# Sheet5.net
KiCad netlist of a schematic drawn in Altium Designer
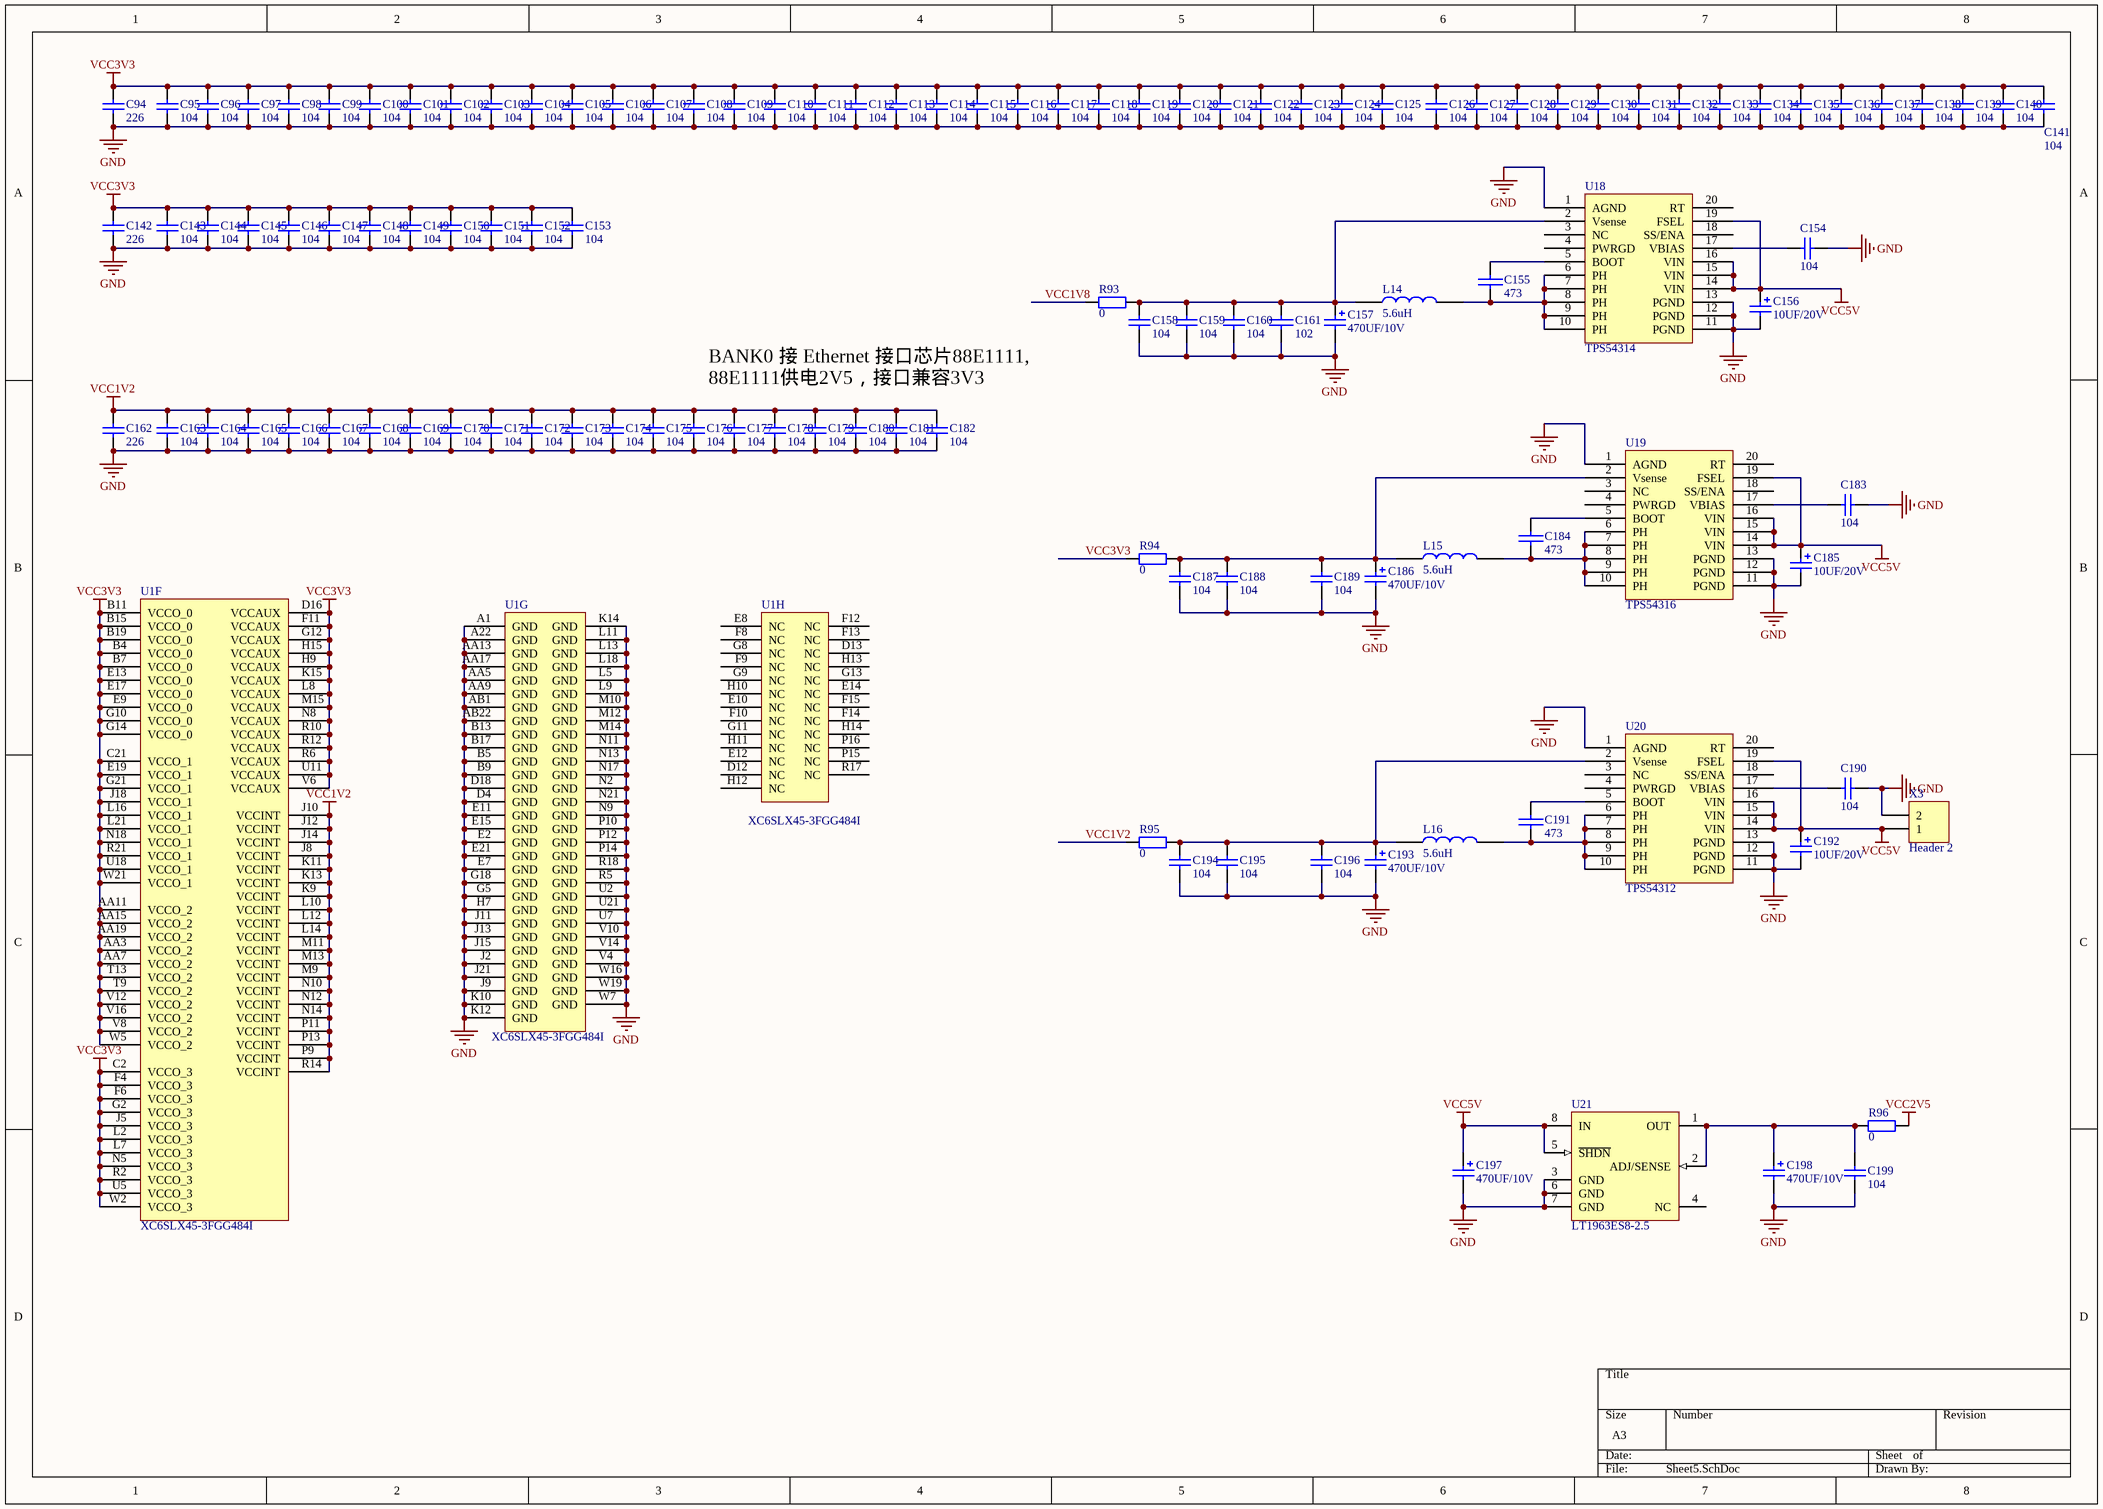
[diagram p0: Sheet5.SchDoc]

(export (version "E")
  (design (tool "Eeschema 10.0.6"))
  (components
    (comp (ref "C94")
      (value "226")
      (footprint "0603")
      (description "Capacitor")
      (fields (field (name "PUBLISHER") "Altium Limited"))
      (libsource (lib "Miscellaneous Devices") (part "Cap"))
    )
    (comp (ref "C95")
      (value "104")
      (footprint "0402")
      (description "Capacitor")
      (fields (field (name "PUBLISHER") "Altium Limited"))
      (libsource (lib "Miscellaneous Devices") (part "Cap"))
    )
    (comp (ref "C96")
      (value "104")
      (footprint "0402")
      (description "Capacitor")
      (fields (field (name "PUBLISHER") "Altium Limited"))
      (libsource (lib "Miscellaneous Devices") (part "Cap"))
    )
    (comp (ref "C97")
      (value "104")
      (footprint "0402")
      (description "Capacitor")
      (fields (field (name "PUBLISHER") "Altium Limited"))
      (libsource (lib "Miscellaneous Devices") (part "Cap"))
    )
    (comp (ref "C98")
      (value "104")
      (footprint "0402")
      (description "Capacitor")
      (fields (field (name "PUBLISHER") "Altium Limited"))
      (libsource (lib "Miscellaneous Devices") (part "Cap"))
    )
    (comp (ref "C99")
      (value "104")
      (footprint "0402")
      (description "Capacitor")
      (fields (field (name "PUBLISHER") "Altium Limited"))
      (libsource (lib "Miscellaneous Devices") (part "Cap"))
    )
    (comp (ref "C100")
      (value "104")
      (footprint "0402")
      (description "Capacitor")
      (fields (field (name "PUBLISHER") "Altium Limited"))
      (libsource (lib "Miscellaneous Devices") (part "Cap"))
    )
    (comp (ref "C101")
      (value "104")
      (footprint "0402")
      (description "Capacitor")
      (fields (field (name "PUBLISHER") "Altium Limited"))
      (libsource (lib "Miscellaneous Devices") (part "Cap"))
    )
    (comp (ref "C102")
      (value "104")
      (footprint "0402")
      (description "Capacitor")
      (fields (field (name "PUBLISHER") "Altium Limited"))
      (libsource (lib "Miscellaneous Devices") (part "Cap"))
    )
    (comp (ref "C103")
      (value "104")
      (footprint "0402")
      (description "Capacitor")
      (fields (field (name "PUBLISHER") "Altium Limited"))
      (libsource (lib "Miscellaneous Devices") (part "Cap"))
    )
    (comp (ref "C104")
      (value "104")
      (footprint "0402")
      (description "Capacitor")
      (fields (field (name "PUBLISHER") "Altium Limited"))
      (libsource (lib "Miscellaneous Devices") (part "Cap"))
    )
    (comp (ref "C105")
      (value "104")
      (footprint "0402")
      (description "Capacitor")
      (fields (field (name "PUBLISHER") "Altium Limited"))
      (libsource (lib "Miscellaneous Devices") (part "Cap"))
    )
    (comp (ref "C106")
      (value "104")
      (footprint "0402")
      (description "Capacitor")
      (fields (field (name "PUBLISHER") "Altium Limited"))
      (libsource (lib "Miscellaneous Devices") (part "Cap"))
    )
    (comp (ref "C107")
      (value "104")
      (footprint "0402")
      (description "Capacitor")
      (fields (field (name "PUBLISHER") "Altium Limited"))
      (libsource (lib "Miscellaneous Devices") (part "Cap"))
    )
    (comp (ref "C108")
      (value "104")
      (footprint "0402")
      (description "Capacitor")
      (fields (field (name "PUBLISHER") "Altium Limited"))
      (libsource (lib "Miscellaneous Devices") (part "Cap"))
    )
    (comp (ref "C109")
      (value "104")
      (footprint "0402")
      (description "Capacitor")
      (fields (field (name "PUBLISHER") "Altium Limited"))
      (libsource (lib "Miscellaneous Devices") (part "Cap"))
    )
    (comp (ref "C110")
      (value "104")
      (footprint "0402")
      (description "Capacitor")
      (fields (field (name "PUBLISHER") "Altium Limited"))
      (libsource (lib "Miscellaneous Devices") (part "Cap"))
    )
    (comp (ref "C111")
      (value "104")
      (footprint "0402")
      (description "Capacitor")
      (fields (field (name "PUBLISHER") "Altium Limited"))
      (libsource (lib "Miscellaneous Devices") (part "Cap"))
    )
    (comp (ref "C112")
      (value "104")
      (footprint "0402")
      (description "Capacitor")
      (fields (field (name "PUBLISHER") "Altium Limited"))
      (libsource (lib "Miscellaneous Devices") (part "Cap"))
    )
    (comp (ref "C113")
      (value "104")
      (footprint "0402")
      (description "Capacitor")
      (fields (field (name "PUBLISHER") "Altium Limited"))
      (libsource (lib "Miscellaneous Devices") (part "Cap"))
    )
    (comp (ref "C114")
      (value "104")
      (footprint "0402")
      (description "Capacitor")
      (fields (field (name "PUBLISHER") "Altium Limited"))
      (libsource (lib "Miscellaneous Devices") (part "Cap"))
    )
    (comp (ref "C115")
      (value "104")
      (footprint "0402")
      (description "Capacitor")
      (fields (field (name "PUBLISHER") "Altium Limited"))
      (libsource (lib "Miscellaneous Devices") (part "Cap"))
    )
    (comp (ref "C116")
      (value "104")
      (footprint "0402")
      (description "Capacitor")
      (fields (field (name "PUBLISHER") "Altium Limited"))
      (libsource (lib "Miscellaneous Devices") (part "Cap"))
    )
    (comp (ref "C117")
      (value "104")
      (footprint "0402")
      (description "Capacitor")
      (fields (field (name "PUBLISHER") "Altium Limited"))
      (libsource (lib "Miscellaneous Devices") (part "Cap"))
    )
    (comp (ref "C118")
      (value "104")
      (footprint "0402")
      (description "Capacitor")
      (fields (field (name "PUBLISHER") "Altium Limited"))
      (libsource (lib "Miscellaneous Devices") (part "Cap"))
    )
    (comp (ref "C119")
      (value "104")
      (footprint "0402")
      (description "Capacitor")
      (fields (field (name "PUBLISHER") "Altium Limited"))
      (libsource (lib "Miscellaneous Devices") (part "Cap"))
    )
    (comp (ref "C120")
      (value "104")
      (footprint "0402")
      (description "Capacitor")
      (fields (field (name "PUBLISHER") "Altium Limited"))
      (libsource (lib "Miscellaneous Devices") (part "Cap"))
    )
    (comp (ref "C121")
      (value "104")
      (footprint "0402")
      (description "Capacitor")
      (fields (field (name "PUBLISHER") "Altium Limited"))
      (libsource (lib "Miscellaneous Devices") (part "Cap"))
    )
    (comp (ref "C122")
      (value "104")
      (footprint "0402")
      (description "Capacitor")
      (fields (field (name "PUBLISHER") "Altium Limited"))
      (libsource (lib "Miscellaneous Devices") (part "Cap"))
    )
    (comp (ref "C123")
      (value "104")
      (footprint "0402")
      (description "Capacitor")
      (fields (field (name "PUBLISHER") "Altium Limited"))
      (libsource (lib "Miscellaneous Devices") (part "Cap"))
    )
    (comp (ref "C124")
      (value "104")
      (footprint "0402")
      (description "Capacitor")
      (fields (field (name "PUBLISHER") "Altium Limited"))
      (libsource (lib "Miscellaneous Devices") (part "Cap"))
    )
    (comp (ref "C125")
      (value "104")
      (footprint "0402")
      (description "Capacitor")
      (fields (field (name "PUBLISHER") "Altium Limited"))
      (libsource (lib "Miscellaneous Devices") (part "Cap"))
    )
    (comp (ref "C126")
      (value "104")
      (footprint "0402")
      (description "Capacitor")
      (fields (field (name "PUBLISHER") "Altium Limited"))
      (libsource (lib "Miscellaneous Devices") (part "Cap"))
    )
    (comp (ref "C127")
      (value "104")
      (footprint "0402")
      (description "Capacitor")
      (fields (field (name "PUBLISHER") "Altium Limited"))
      (libsource (lib "Miscellaneous Devices") (part "Cap"))
    )
    (comp (ref "C128")
      (value "104")
      (footprint "0402")
      (description "Capacitor")
      (fields (field (name "PUBLISHER") "Altium Limited"))
      (libsource (lib "Miscellaneous Devices") (part "Cap"))
    )
    (comp (ref "C129")
      (value "104")
      (footprint "0402")
      (description "Capacitor")
      (fields (field (name "PUBLISHER") "Altium Limited"))
      (libsource (lib "Miscellaneous Devices") (part "Cap"))
    )
    (comp (ref "C130")
      (value "104")
      (footprint "0402")
      (description "Capacitor")
      (fields (field (name "PUBLISHER") "Altium Limited"))
      (libsource (lib "Miscellaneous Devices") (part "Cap"))
    )
    (comp (ref "C131")
      (value "104")
      (footprint "0402")
      (description "Capacitor")
      (fields (field (name "PUBLISHER") "Altium Limited"))
      (libsource (lib "Miscellaneous Devices") (part "Cap"))
    )
    (comp (ref "C132")
      (value "104")
      (footprint "0402")
      (description "Capacitor")
      (fields (field (name "PUBLISHER") "Altium Limited"))
      (libsource (lib "Miscellaneous Devices") (part "Cap"))
    )
    (comp (ref "C133")
      (value "104")
      (footprint "0402")
      (description "Capacitor")
      (fields (field (name "PUBLISHER") "Altium Limited"))
      (libsource (lib "Miscellaneous Devices") (part "Cap"))
    )
    (comp (ref "C134")
      (value "104")
      (footprint "0402")
      (description "Capacitor")
      (fields (field (name "PUBLISHER") "Altium Limited"))
      (libsource (lib "Miscellaneous Devices") (part "Cap"))
    )
    (comp (ref "C135")
      (value "104")
      (footprint "0402")
      (description "Capacitor")
      (fields (field (name "PUBLISHER") "Altium Limited"))
      (libsource (lib "Miscellaneous Devices") (part "Cap"))
    )
    (comp (ref "C136")
      (value "104")
      (footprint "0402")
      (description "Capacitor")
      (fields (field (name "PUBLISHER") "Altium Limited"))
      (libsource (lib "Miscellaneous Devices") (part "Cap"))
    )
    (comp (ref "C137")
      (value "104")
      (footprint "0402")
      (description "Capacitor")
      (fields (field (name "PUBLISHER") "Altium Limited"))
      (libsource (lib "Miscellaneous Devices") (part "Cap"))
    )
    (comp (ref "C138")
      (value "104")
      (footprint "0402")
      (description "Capacitor")
      (fields (field (name "PUBLISHER") "Altium Limited"))
      (libsource (lib "Miscellaneous Devices") (part "Cap"))
    )
    (comp (ref "C139")
      (value "104")
      (footprint "0402")
      (description "Capacitor")
      (fields (field (name "PUBLISHER") "Altium Limited"))
      (libsource (lib "Miscellaneous Devices") (part "Cap"))
    )
    (comp (ref "C140")
      (value "104")
      (footprint "0402")
      (description "Capacitor")
      (fields (field (name "PUBLISHER") "Altium Limited"))
      (libsource (lib "Miscellaneous Devices") (part "Cap"))
    )
    (comp (ref "C141")
      (value "104")
      (footprint "0402")
      (description "Capacitor")
      (fields (field (name "PUBLISHER") "Altium Limited"))
      (libsource (lib "Miscellaneous Devices") (part "Cap"))
    )
    (comp (ref "C142")
      (value "226")
      (footprint "0603")
      (description "Capacitor")
      (fields (field (name "PUBLISHER") "Altium Limited"))
      (libsource (lib "Miscellaneous Devices") (part "Cap"))
    )
    (comp (ref "C143")
      (value "104")
      (footprint "0402")
      (description "Capacitor")
      (fields (field (name "PUBLISHER") "Altium Limited"))
      (libsource (lib "Miscellaneous Devices") (part "Cap"))
    )
    (comp (ref "C144")
      (value "104")
      (footprint "0402")
      (description "Capacitor")
      (fields (field (name "PUBLISHER") "Altium Limited"))
      (libsource (lib "Miscellaneous Devices") (part "Cap"))
    )
    (comp (ref "C145")
      (value "104")
      (footprint "0402")
      (description "Capacitor")
      (fields (field (name "PUBLISHER") "Altium Limited"))
      (libsource (lib "Miscellaneous Devices") (part "Cap"))
    )
    (comp (ref "C146")
      (value "104")
      (footprint "0402")
      (description "Capacitor")
      (fields (field (name "PUBLISHER") "Altium Limited"))
      (libsource (lib "Miscellaneous Devices") (part "Cap"))
    )
    (comp (ref "C147")
      (value "104")
      (footprint "0402")
      (description "Capacitor")
      (fields (field (name "PUBLISHER") "Altium Limited"))
      (libsource (lib "Miscellaneous Devices") (part "Cap"))
    )
    (comp (ref "C148")
      (value "104")
      (footprint "0402")
      (description "Capacitor")
      (fields (field (name "PUBLISHER") "Altium Limited"))
      (libsource (lib "Miscellaneous Devices") (part "Cap"))
    )
    (comp (ref "C149")
      (value "104")
      (footprint "0402")
      (description "Capacitor")
      (fields (field (name "PUBLISHER") "Altium Limited"))
      (libsource (lib "Miscellaneous Devices") (part "Cap"))
    )
    (comp (ref "C150")
      (value "104")
      (footprint "0402")
      (description "Capacitor")
      (fields (field (name "PUBLISHER") "Altium Limited"))
      (libsource (lib "Miscellaneous Devices") (part "Cap"))
    )
    (comp (ref "C151")
      (value "104")
      (footprint "0402")
      (description "Capacitor")
      (fields (field (name "PUBLISHER") "Altium Limited"))
      (libsource (lib "Miscellaneous Devices") (part "Cap"))
    )
    (comp (ref "C152")
      (value "104")
      (footprint "0402")
      (description "Capacitor")
      (fields (field (name "PUBLISHER") "Altium Limited"))
      (libsource (lib "Miscellaneous Devices") (part "Cap"))
    )
    (comp (ref "C153")
      (value "104")
      (footprint "0402")
      (description "Capacitor")
      (fields (field (name "PUBLISHER") "Altium Limited"))
      (libsource (lib "Miscellaneous Devices") (part "Cap"))
    )
    (comp (ref "C154")
      (value "104")
      (footprint "0402")
      (description "Capacitor")
      (fields (field (name "PUBLISHER") "Altium Limited"))
      (libsource (lib "Miscellaneous Devices") (part "Cap"))
    )
    (comp (ref "C155")
      (value "473")
      (footprint "0402")
      (description "Capacitor")
      (libsource (lib "*") (part "CAP"))
    )
    (comp (ref "C156")
      (value "10UF/20V")
      (footprint "CAP-B")
      (description "Polarized Capacitor (Axial)")
      (fields (field (name "PUBLISHER") "Altium Limited"))
      (libsource (lib "Miscellaneous Devices") (part "Cap Pol2"))
    )
    (comp (ref "C157")
      (value "470UF/10V")
      (footprint "CAP-D")
      (description "Polarized Capacitor (Axial)")
      (fields (field (name "PUBLISHER") "Altium Limited"))
      (libsource (lib "Miscellaneous Devices") (part "Cap Pol2"))
    )
    (comp (ref "C158")
      (value "104")
      (footprint "0402")
      (description "Capacitor")
      (fields (field (name "PUBLISHER") "Altium Limited"))
      (libsource (lib "Miscellaneous Devices") (part "Cap"))
    )
    (comp (ref "C159")
      (value "104")
      (footprint "0402")
      (description "Capacitor")
      (fields (field (name "PUBLISHER") "Altium Limited"))
      (libsource (lib "Miscellaneous Devices") (part "Cap"))
    )
    (comp (ref "C160")
      (value "104")
      (footprint "0402")
      (description "Capacitor")
      (fields (field (name "PUBLISHER") "Altium Limited"))
      (libsource (lib "Miscellaneous Devices") (part "Cap"))
    )
    (comp (ref "C161")
      (value "102")
      (footprint "0402")
      (description "Capacitor")
      (libsource (lib "*") (part "CAP"))
    )
    (comp (ref "C162")
      (value "226")
      (footprint "0603")
      (description "Capacitor")
      (fields (field (name "PUBLISHER") "Altium Limited"))
      (libsource (lib "Miscellaneous Devices") (part "Cap"))
    )
    (comp (ref "C163")
      (value "104")
      (footprint "0402")
      (description "Capacitor")
      (fields (field (name "PUBLISHER") "Altium Limited"))
      (libsource (lib "Miscellaneous Devices") (part "Cap"))
    )
    (comp (ref "C164")
      (value "104")
      (footprint "0402")
      (description "Capacitor")
      (fields (field (name "PUBLISHER") "Altium Limited"))
      (libsource (lib "Miscellaneous Devices") (part "Cap"))
    )
    (comp (ref "C165")
      (value "104")
      (footprint "0402")
      (description "Capacitor")
      (fields (field (name "PUBLISHER") "Altium Limited"))
      (libsource (lib "Miscellaneous Devices") (part "Cap"))
    )
    (comp (ref "C166")
      (value "104")
      (footprint "0402")
      (description "Capacitor")
      (fields (field (name "PUBLISHER") "Altium Limited"))
      (libsource (lib "Miscellaneous Devices") (part "Cap"))
    )
    (comp (ref "C167")
      (value "104")
      (footprint "0402")
      (description "Capacitor")
      (fields (field (name "PUBLISHER") "Altium Limited"))
      (libsource (lib "Miscellaneous Devices") (part "Cap"))
    )
    (comp (ref "C168")
      (value "104")
      (footprint "0402")
      (description "Capacitor")
      (fields (field (name "PUBLISHER") "Altium Limited"))
      (libsource (lib "Miscellaneous Devices") (part "Cap"))
    )
    (comp (ref "C169")
      (value "104")
      (footprint "0402")
      (description "Capacitor")
      (fields (field (name "PUBLISHER") "Altium Limited"))
      (libsource (lib "Miscellaneous Devices") (part "Cap"))
    )
    (comp (ref "C170")
      (value "104")
      (footprint "0402")
      (description "Capacitor")
      (fields (field (name "PUBLISHER") "Altium Limited"))
      (libsource (lib "Miscellaneous Devices") (part "Cap"))
    )
    (comp (ref "C171")
      (value "104")
      (footprint "0402")
      (description "Capacitor")
      (fields (field (name "PUBLISHER") "Altium Limited"))
      (libsource (lib "Miscellaneous Devices") (part "Cap"))
    )
    (comp (ref "C172")
      (value "104")
      (footprint "0402")
      (description "Capacitor")
      (fields (field (name "PUBLISHER") "Altium Limited"))
      (libsource (lib "Miscellaneous Devices") (part "Cap"))
    )
    (comp (ref "C173")
      (value "104")
      (footprint "0402")
      (description "Capacitor")
      (fields (field (name "PUBLISHER") "Altium Limited"))
      (libsource (lib "Miscellaneous Devices") (part "Cap"))
    )
    (comp (ref "C174")
      (value "104")
      (footprint "0402")
      (description "Capacitor")
      (fields (field (name "PUBLISHER") "Altium Limited"))
      (libsource (lib "Miscellaneous Devices") (part "Cap"))
    )
    (comp (ref "C175")
      (value "104")
      (footprint "0402")
      (description "Capacitor")
      (fields (field (name "PUBLISHER") "Altium Limited"))
      (libsource (lib "Miscellaneous Devices") (part "Cap"))
    )
    (comp (ref "C176")
      (value "104")
      (footprint "0402")
      (description "Capacitor")
      (fields (field (name "PUBLISHER") "Altium Limited"))
      (libsource (lib "Miscellaneous Devices") (part "Cap"))
    )
    (comp (ref "C177")
      (value "104")
      (footprint "0402")
      (description "Capacitor")
      (fields (field (name "PUBLISHER") "Altium Limited"))
      (libsource (lib "Miscellaneous Devices") (part "Cap"))
    )
    (comp (ref "C178")
      (value "104")
      (footprint "0402")
      (description "Capacitor")
      (fields (field (name "PUBLISHER") "Altium Limited"))
      (libsource (lib "Miscellaneous Devices") (part "Cap"))
    )
    (comp (ref "C179")
      (value "104")
      (footprint "0402")
      (description "Capacitor")
      (fields (field (name "PUBLISHER") "Altium Limited"))
      (libsource (lib "Miscellaneous Devices") (part "Cap"))
    )
    (comp (ref "C180")
      (value "104")
      (footprint "0402")
      (description "Capacitor")
      (fields (field (name "PUBLISHER") "Altium Limited"))
      (libsource (lib "Miscellaneous Devices") (part "Cap"))
    )
    (comp (ref "C181")
      (value "104")
      (footprint "0402")
      (description "Capacitor")
      (fields (field (name "PUBLISHER") "Altium Limited"))
      (libsource (lib "Miscellaneous Devices") (part "Cap"))
    )
    (comp (ref "C182")
      (value "104")
      (footprint "0402")
      (description "Capacitor")
      (fields (field (name "PUBLISHER") "Altium Limited"))
      (libsource (lib "Miscellaneous Devices") (part "Cap"))
    )
    (comp (ref "C183")
      (value "104")
      (footprint "0402")
      (description "Capacitor")
      (fields (field (name "PUBLISHER") "Altium Limited"))
      (libsource (lib "Miscellaneous Devices") (part "Cap"))
    )
    (comp (ref "C184")
      (value "473")
      (footprint "0402")
      (description "Capacitor")
      (libsource (lib "*") (part "CAP"))
    )
    (comp (ref "C185")
      (value "10UF/20V")
      (footprint "CAP-B")
      (description "Polarized Capacitor (Axial)")
      (fields (field (name "PUBLISHER") "Altium Limited"))
      (libsource (lib "Miscellaneous Devices") (part "Cap Pol2"))
    )
    (comp (ref "C186")
      (value "470UF/10V")
      (footprint "CAP-D")
      (description "Polarized Capacitor (Axial)")
      (fields (field (name "PUBLISHER") "Altium Limited"))
      (libsource (lib "Miscellaneous Devices") (part "Cap Pol2"))
    )
    (comp (ref "C187")
      (value "104")
      (footprint "0402")
      (description "Capacitor")
      (fields (field (name "PUBLISHER") "Altium Limited"))
      (libsource (lib "Miscellaneous Devices") (part "Cap"))
    )
    (comp (ref "C188")
      (value "104")
      (footprint "0402")
      (description "Capacitor")
      (fields (field (name "PUBLISHER") "Altium Limited"))
      (libsource (lib "Miscellaneous Devices") (part "Cap"))
    )
    (comp (ref "C189")
      (value "104")
      (footprint "0402")
      (description "Capacitor")
      (fields (field (name "PUBLISHER") "Altium Limited"))
      (libsource (lib "Miscellaneous Devices") (part "Cap"))
    )
    (comp (ref "C190")
      (value "104")
      (footprint "0402")
      (description "Capacitor")
      (fields (field (name "PUBLISHER") "Altium Limited"))
      (libsource (lib "Miscellaneous Devices") (part "Cap"))
    )
    (comp (ref "C191")
      (value "473")
      (footprint "0402")
      (description "Capacitor")
      (libsource (lib "*") (part "CAP"))
    )
    (comp (ref "C192")
      (value "10UF/20V")
      (footprint "CAP-B")
      (description "Polarized Capacitor (Axial)")
      (fields (field (name "PUBLISHER") "Altium Limited"))
      (libsource (lib "Miscellaneous Devices") (part "Cap Pol2"))
    )
    (comp (ref "C193")
      (value "470UF/10V")
      (footprint "CAP-D")
      (description "Polarized Capacitor (Axial)")
      (fields (field (name "PUBLISHER") "Altium Limited"))
      (libsource (lib "Miscellaneous Devices") (part "Cap Pol2"))
    )
    (comp (ref "C194")
      (value "104")
      (footprint "0402")
      (description "Capacitor")
      (fields (field (name "PUBLISHER") "Altium Limited"))
      (libsource (lib "Miscellaneous Devices") (part "Cap"))
    )
    (comp (ref "C195")
      (value "104")
      (footprint "0402")
      (description "Capacitor")
      (fields (field (name "PUBLISHER") "Altium Limited"))
      (libsource (lib "Miscellaneous Devices") (part "Cap"))
    )
    (comp (ref "C196")
      (value "104")
      (footprint "0402")
      (description "Capacitor")
      (fields (field (name "PUBLISHER") "Altium Limited"))
      (libsource (lib "Miscellaneous Devices") (part "Cap"))
    )
    (comp (ref "C197")
      (value "470UF/10V")
      (footprint "CAP-D")
      (description "Polarized Capacitor (Axial)")
      (fields (field (name "PUBLISHER") "Altium Limited"))
      (libsource (lib "Miscellaneous Devices") (part "Cap Pol2"))
    )
    (comp (ref "C198")
      (value "470UF/10V")
      (footprint "CAP-D")
      (description "Polarized Capacitor (Axial)")
      (fields (field (name "PUBLISHER") "Altium Limited"))
      (libsource (lib "Miscellaneous Devices") (part "Cap Pol2"))
    )
    (comp (ref "C199")
      (value "104")
      (footprint "0402")
      (description "Capacitor")
      (fields (field (name "PUBLISHER") "Altium Limited"))
      (libsource (lib "Miscellaneous Devices") (part "Cap"))
    )
    (comp (ref "L14") (value "5.6uH") (footprint "L5R2") (libsource (lib "*") (part "INDUCTOR1")))
    (comp (ref "L15") (value "5.6uH") (footprint "L5R2") (libsource (lib "*") (part "INDUCTOR1")))
    (comp (ref "L16") (value "5.6uH") (footprint "L5R2") (libsource (lib "*") (part "INDUCTOR1")))
    (comp (ref "R93")
      (value "0")
      (footprint "0603")
      (description "Resistor")
      (fields (field (name "PUBLISHER") "Altium Limited"))
      (libsource (lib "Miscellaneous Devices") (part "Res2"))
    )
    (comp (ref "R94")
      (value "0")
      (footprint "0603")
      (description "Resistor")
      (fields (field (name "PUBLISHER") "Altium Limited"))
      (libsource (lib "Miscellaneous Devices") (part "Res2"))
    )
    (comp (ref "R95")
      (value "0")
      (footprint "0603")
      (description "Resistor")
      (fields (field (name "PUBLISHER") "Altium Limited"))
      (libsource (lib "Miscellaneous Devices") (part "Res2"))
    )
    (comp (ref "R96")
      (value "0")
      (footprint "0603")
      (description "Resistor")
      (fields (field (name "PUBLISHER") "Altium Limited"))
      (libsource (lib "Miscellaneous Devices") (part "Res2"))
    )
    (comp (ref "U1")
      (value "XC6SLX45-3FGG484I")
      (footprint "FGG484")
      (fields (field (name "PUBLISHER") "Altium Limited"))
      (libsource (lib "Xilinx Spartan-6") (part "XC6SLX45-3FGG484I"))
    )
    (comp (ref "U18")
      (value "TPS54314")
      (footprint "SOP20")
      (description "TPS54312")
      (libsource (lib "*") (part "TPS54312"))
    )
    (comp (ref "U19")
      (value "TPS54316")
      (footprint "SOP20")
      (description "TPS54312")
      (libsource (lib "*") (part "TPS54312"))
    )
    (comp (ref "U20") (value "TPS54312") (footprint "SOP20") (libsource (lib "*") (part "TPS54312")))
    (comp (ref "U21")
      (value "LT1963ES8-2.5")
      (footprint "so_8")
      (description "300mA, Low Noise, Micropower Low Dropout Regulator")
      (fields (field (name "PUBLISHER") "Altium Limited"))
      (libsource (lib "Mpd_Fpga_2") (part "LT1962EMS8"))
    )
    (comp (ref "X3")
      (value "Header 2")
      (footprint "HDR1X2")
      (description "Header, 2-Pin")
      (fields (field (name "PUBLISHER") "Altium Limited"))
      (libsource (lib "Miscellaneous Connectors") (part "Header 2"))
    )
  )
  (nets
    (net (code "1") (name "/VCC1V8") (class "Default")
      (node (ref "R93") (pin "2") (pinfunction "2_2") (pintype "passive"))
    )
    (net (code "2") (name "GND") (class "Default")
      (node (ref "C100") (pin "1") (pinfunction "1_1") (pintype "passive"))
      (node (ref "C101") (pin "1") (pinfunction "1_1") (pintype "passive"))
      (node (ref "C102") (pin "1") (pinfunction "1_1") (pintype "passive"))
      (node (ref "C103") (pin "1") (pinfunction "1_1") (pintype "passive"))
      (node (ref "C104") (pin "1") (pinfunction "1_1") (pintype "passive"))
      (node (ref "C105") (pin "1") (pinfunction "1_1") (pintype "passive"))
      (node (ref "C106") (pin "1") (pinfunction "1_1") (pintype "passive"))
      (node (ref "C107") (pin "1") (pinfunction "1_1") (pintype "passive"))
      (node (ref "C108") (pin "1") (pinfunction "1_1") (pintype "passive"))
      (node (ref "C109") (pin "1") (pinfunction "1_1") (pintype "passive"))
      (node (ref "C110") (pin "1") (pinfunction "1_1") (pintype "passive"))
      (node (ref "C111") (pin "1") (pinfunction "1_1") (pintype "passive"))
      (node (ref "C112") (pin "1") (pinfunction "1_1") (pintype "passive"))
      (node (ref "C113") (pin "1") (pinfunction "1_1") (pintype "passive"))
      (node (ref "C114") (pin "1") (pinfunction "1_1") (pintype "passive"))
      (node (ref "C115") (pin "1") (pinfunction "1_1") (pintype "passive"))
      (node (ref "C116") (pin "1") (pinfunction "1_1") (pintype "passive"))
      (node (ref "C117") (pin "1") (pinfunction "1_1") (pintype "passive"))
      (node (ref "C118") (pin "1") (pinfunction "1_1") (pintype "passive"))
      (node (ref "C119") (pin "1") (pinfunction "1_1") (pintype "passive"))
      (node (ref "C120") (pin "1") (pinfunction "1_1") (pintype "passive"))
      (node (ref "C121") (pin "1") (pinfunction "1_1") (pintype "passive"))
      (node (ref "C122") (pin "1") (pinfunction "1_1") (pintype "passive"))
      (node (ref "C123") (pin "1") (pinfunction "1_1") (pintype "passive"))
      (node (ref "C124") (pin "1") (pinfunction "1_1") (pintype "passive"))
      (node (ref "C125") (pin "1") (pinfunction "1_1") (pintype "passive"))
      (node (ref "C126") (pin "1") (pinfunction "1_1") (pintype "passive"))
      (node (ref "C127") (pin "1") (pinfunction "1_1") (pintype "passive"))
      (node (ref "C128") (pin "1") (pinfunction "1_1") (pintype "passive"))
      (node (ref "C129") (pin "1") (pinfunction "1_1") (pintype "passive"))
      (node (ref "C130") (pin "1") (pinfunction "1_1") (pintype "passive"))
      (node (ref "C131") (pin "1") (pinfunction "1_1") (pintype "passive"))
      (node (ref "C132") (pin "1") (pinfunction "1_1") (pintype "passive"))
      (node (ref "C133") (pin "1") (pinfunction "1_1") (pintype "passive"))
      (node (ref "C134") (pin "1") (pinfunction "1_1") (pintype "passive"))
      (node (ref "C135") (pin "1") (pinfunction "1_1") (pintype "passive"))
      (node (ref "C136") (pin "1") (pinfunction "1_1") (pintype "passive"))
      (node (ref "C137") (pin "1") (pinfunction "1_1") (pintype "passive"))
      (node (ref "C138") (pin "1") (pinfunction "1_1") (pintype "passive"))
      (node (ref "C139") (pin "1") (pinfunction "1_1") (pintype "passive"))
      (node (ref "C140") (pin "1") (pinfunction "1_1") (pintype "passive"))
      (node (ref "C141") (pin "1") (pinfunction "1_1") (pintype "passive"))
      (node (ref "C142") (pin "1") (pinfunction "1_1") (pintype "passive"))
      (node (ref "C143") (pin "1") (pinfunction "1_1") (pintype "passive"))
      (node (ref "C144") (pin "1") (pinfunction "1_1") (pintype "passive"))
      (node (ref "C145") (pin "1") (pinfunction "1_1") (pintype "passive"))
      (node (ref "C146") (pin "1") (pinfunction "1_1") (pintype "passive"))
      (node (ref "C147") (pin "1") (pinfunction "1_1") (pintype "passive"))
      (node (ref "C148") (pin "1") (pinfunction "1_1") (pintype "passive"))
      (node (ref "C149") (pin "1") (pinfunction "1_1") (pintype "passive"))
      (node (ref "C150") (pin "1") (pinfunction "1_1") (pintype "passive"))
      (node (ref "C151") (pin "1") (pinfunction "1_1") (pintype "passive"))
      (node (ref "C152") (pin "1") (pinfunction "1_1") (pintype "passive"))
      (node (ref "C153") (pin "1") (pinfunction "1_1") (pintype "passive"))
      (node (ref "C154") (pin "1") (pinfunction "1_1") (pintype "passive"))
      (node (ref "C156") (pin "2") (pinfunction "2_2") (pintype "passive"))
      (node (ref "C157") (pin "2") (pinfunction "2_2") (pintype "passive"))
      (node (ref "C158") (pin "1") (pinfunction "1_1") (pintype "passive"))
      (node (ref "C159") (pin "1") (pinfunction "1_1") (pintype "passive"))
      (node (ref "C160") (pin "1") (pinfunction "1_1") (pintype "passive"))
      (node (ref "C161") (pin "1") (pinfunction "1_1") (pintype "passive"))
      (node (ref "C162") (pin "1") (pinfunction "1_1") (pintype "passive"))
      (node (ref "C163") (pin "1") (pinfunction "1_1") (pintype "passive"))
      (node (ref "C164") (pin "1") (pinfunction "1_1") (pintype "passive"))
      (node (ref "C165") (pin "1") (pinfunction "1_1") (pintype "passive"))
      (node (ref "C166") (pin "1") (pinfunction "1_1") (pintype "passive"))
      (node (ref "C167") (pin "1") (pinfunction "1_1") (pintype "passive"))
      (node (ref "C168") (pin "1") (pinfunction "1_1") (pintype "passive"))
      (node (ref "C169") (pin "1") (pinfunction "1_1") (pintype "passive"))
      (node (ref "C170") (pin "1") (pinfunction "1_1") (pintype "passive"))
      (node (ref "C171") (pin "1") (pinfunction "1_1") (pintype "passive"))
      (node (ref "C172") (pin "1") (pinfunction "1_1") (pintype "passive"))
      (node (ref "C173") (pin "1") (pinfunction "1_1") (pintype "passive"))
      (node (ref "C174") (pin "1") (pinfunction "1_1") (pintype "passive"))
      (node (ref "C175") (pin "1") (pinfunction "1_1") (pintype "passive"))
      (node (ref "C176") (pin "1") (pinfunction "1_1") (pintype "passive"))
      (node (ref "C177") (pin "1") (pinfunction "1_1") (pintype "passive"))
      (node (ref "C178") (pin "1") (pinfunction "1_1") (pintype "passive"))
      (node (ref "C179") (pin "1") (pinfunction "1_1") (pintype "passive"))
      (node (ref "C180") (pin "1") (pinfunction "1_1") (pintype "passive"))
      (node (ref "C181") (pin "1") (pinfunction "1_1") (pintype "passive"))
      (node (ref "C182") (pin "1") (pinfunction "1_1") (pintype "passive"))
      (node (ref "C183") (pin "1") (pinfunction "1_1") (pintype "passive"))
      (node (ref "C185") (pin "2") (pinfunction "2_2") (pintype "passive"))
      (node (ref "C186") (pin "2") (pinfunction "2_2") (pintype "passive"))
      (node (ref "C187") (pin "1") (pinfunction "1_1") (pintype "passive"))
      (node (ref "C188") (pin "1") (pinfunction "1_1") (pintype "passive"))
      (node (ref "C189") (pin "1") (pinfunction "1_1") (pintype "passive"))
      (node (ref "C190") (pin "1") (pinfunction "1_1") (pintype "passive"))
      (node (ref "C192") (pin "2") (pinfunction "2_2") (pintype "passive"))
      (node (ref "C193") (pin "2") (pinfunction "2_2") (pintype "passive"))
      (node (ref "C194") (pin "1") (pinfunction "1_1") (pintype "passive"))
      (node (ref "C195") (pin "1") (pinfunction "1_1") (pintype "passive"))
      (node (ref "C196") (pin "1") (pinfunction "1_1") (pintype "passive"))
      (node (ref "C197") (pin "2") (pinfunction "2_2") (pintype "passive"))
      (node (ref "C198") (pin "2") (pinfunction "2_2") (pintype "passive"))
      (node (ref "C199") (pin "1") (pinfunction "1_1") (pintype "passive"))
      (node (ref "C94") (pin "1") (pinfunction "1_1") (pintype "passive"))
      (node (ref "C95") (pin "1") (pinfunction "1_1") (pintype "passive"))
      (node (ref "C96") (pin "1") (pinfunction "1_1") (pintype "passive"))
      (node (ref "C97") (pin "1") (pinfunction "1_1") (pintype "passive"))
      (node (ref "C98") (pin "1") (pinfunction "1_1") (pintype "passive"))
      (node (ref "C99") (pin "1") (pinfunction "1_1") (pintype "passive"))
      (node (ref "U1") (pin "A1") (pinfunction "GND_A1") (pintype "power_in"))
      (node (ref "U1") (pin "A22") (pinfunction "GND_A22") (pintype "power_in"))
      (node (ref "U1") (pin "AA13") (pinfunction "GND_AA13") (pintype "power_in"))
      (node (ref "U1") (pin "AA17") (pinfunction "GND_AA17") (pintype "power_in"))
      (node (ref "U1") (pin "AA5") (pinfunction "GND_AA5") (pintype "power_in"))
      (node (ref "U1") (pin "AA9") (pinfunction "GND_AA9") (pintype "power_in"))
      (node (ref "U1") (pin "AB1") (pinfunction "GND_AB1") (pintype "power_in"))
      (node (ref "U1") (pin "AB22") (pinfunction "GND_AB22") (pintype "power_in"))
      (node (ref "U1") (pin "B13") (pinfunction "GND_B13") (pintype "power_in"))
      (node (ref "U1") (pin "B17") (pinfunction "GND_B17") (pintype "power_in"))
      (node (ref "U1") (pin "B5") (pinfunction "GND_B5") (pintype "power_in"))
      (node (ref "U1") (pin "B9") (pinfunction "GND_B9") (pintype "power_in"))
      (node (ref "U1") (pin "D18") (pinfunction "GND_D18") (pintype "power_in"))
      (node (ref "U1") (pin "D4") (pinfunction "GND_D4") (pintype "power_in"))
      (node (ref "U1") (pin "E11") (pinfunction "GND_E11") (pintype "power_in"))
      (node (ref "U1") (pin "E15") (pinfunction "GND_E15") (pintype "power_in"))
      (node (ref "U1") (pin "E2") (pinfunction "GND_E2") (pintype "power_in"))
      (node (ref "U1") (pin "E21") (pinfunction "GND_E21") (pintype "power_in"))
      (node (ref "U1") (pin "E7") (pinfunction "GND_E7") (pintype "power_in"))
      (node (ref "U1") (pin "G18") (pinfunction "GND_G18") (pintype "power_in"))
      (node (ref "U1") (pin "G5") (pinfunction "GND_G5") (pintype "power_in"))
      (node (ref "U1") (pin "H7") (pinfunction "GND_H7") (pintype "power_in"))
      (node (ref "U1") (pin "J11") (pinfunction "GND_J11") (pintype "power_in"))
      (node (ref "U1") (pin "J13") (pinfunction "GND_J13") (pintype "power_in"))
      (node (ref "U1") (pin "J15") (pinfunction "GND_J15") (pintype "power_in"))
      (node (ref "U1") (pin "J2") (pinfunction "GND_J2") (pintype "power_in"))
      (node (ref "U1") (pin "J21") (pinfunction "GND_J21") (pintype "power_in"))
      (node (ref "U1") (pin "J9") (pinfunction "GND_J9") (pintype "power_in"))
      (node (ref "U1") (pin "K10") (pinfunction "GND_K10") (pintype "power_in"))
      (node (ref "U1") (pin "K12") (pinfunction "GND_K12") (pintype "power_in"))
      (node (ref "U1") (pin "K14") (pinfunction "GND_K14") (pintype "power_in"))
      (node (ref "U1") (pin "L11") (pinfunction "GND_L11") (pintype "power_in"))
      (node (ref "U1") (pin "L13") (pinfunction "GND_L13") (pintype "power_in"))
      (node (ref "U1") (pin "L18") (pinfunction "GND_L18") (pintype "power_in"))
      (node (ref "U1") (pin "L5") (pinfunction "GND_L5") (pintype "power_in"))
      (node (ref "U1") (pin "L9") (pinfunction "GND_L9") (pintype "power_in"))
      (node (ref "U1") (pin "M10") (pinfunction "GND_M10") (pintype "power_in"))
      (node (ref "U1") (pin "M12") (pinfunction "GND_M12") (pintype "power_in"))
      (node (ref "U1") (pin "M14") (pinfunction "GND_M14") (pintype "power_in"))
      (node (ref "U1") (pin "N11") (pinfunction "GND_N11") (pintype "power_in"))
      (node (ref "U1") (pin "N13") (pinfunction "GND_N13") (pintype "power_in"))
      (node (ref "U1") (pin "N17") (pinfunction "GND_N17") (pintype "power_in"))
      (node (ref "U1") (pin "N2") (pinfunction "GND_N2") (pintype "power_in"))
      (node (ref "U1") (pin "N21") (pinfunction "GND_N21") (pintype "power_in"))
      (node (ref "U1") (pin "N9") (pinfunction "GND_N9") (pintype "power_in"))
      (node (ref "U1") (pin "P10") (pinfunction "GND_P10") (pintype "power_in"))
      (node (ref "U1") (pin "P12") (pinfunction "GND_P12") (pintype "power_in"))
      (node (ref "U1") (pin "P14") (pinfunction "GND_P14") (pintype "power_in"))
      (node (ref "U1") (pin "R18") (pinfunction "GND_R18") (pintype "power_in"))
      (node (ref "U1") (pin "R5") (pinfunction "GND_R5") (pintype "power_in"))
      (node (ref "U1") (pin "U2") (pinfunction "GND_U2") (pintype "power_in"))
      (node (ref "U1") (pin "U21") (pinfunction "GND_U21") (pintype "power_in"))
      (node (ref "U1") (pin "U7") (pinfunction "GND_U7") (pintype "power_in"))
      (node (ref "U1") (pin "V10") (pinfunction "GND_V10") (pintype "power_in"))
      (node (ref "U1") (pin "V14") (pinfunction "GND_V14") (pintype "power_in"))
      (node (ref "U1") (pin "V4") (pinfunction "GND_V4") (pintype "power_in"))
      (node (ref "U1") (pin "W16") (pinfunction "GND_W16") (pintype "power_in"))
      (node (ref "U1") (pin "W19") (pinfunction "GND_W19") (pintype "power_in"))
      (node (ref "U1") (pin "W7") (pinfunction "GND_W7") (pintype "power_in"))
      (node (ref "U18") (pin "1") (pinfunction "AGND_1") (pintype "passive"))
      (node (ref "U18") (pin "11") (pinfunction "PGND_11") (pintype "passive"))
      (node (ref "U18") (pin "12") (pinfunction "PGND_12") (pintype "passive"))
      (node (ref "U18") (pin "13") (pinfunction "PGND_13") (pintype "passive"))
      (node (ref "U19") (pin "1") (pinfunction "AGND_1") (pintype "passive"))
      (node (ref "U19") (pin "11") (pinfunction "PGND_11") (pintype "passive"))
      (node (ref "U19") (pin "12") (pinfunction "PGND_12") (pintype "passive"))
      (node (ref "U19") (pin "13") (pinfunction "PGND_13") (pintype "passive"))
      (node (ref "U20") (pin "1") (pinfunction "AGND_1") (pintype "passive"))
      (node (ref "U20") (pin "11") (pinfunction "PGND_11") (pintype "passive"))
      (node (ref "U20") (pin "12") (pinfunction "PGND_12") (pintype "passive"))
      (node (ref "U20") (pin "13") (pinfunction "PGND_13") (pintype "passive"))
      (node (ref "U21") (pin "3") (pinfunction "GND_3") (pintype "power_in"))
      (node (ref "U21") (pin "6") (pinfunction "GND_6") (pintype "power_in"))
      (node (ref "U21") (pin "7") (pinfunction "GND_7") (pintype "power_in"))
      (node (ref "X3") (pin "2") (pinfunction "2_2") (pintype "passive"))
    )
    (net (code "3") (name "Net-(C155-Pad1)") (class "Default")
      (node (ref "C155") (pin "1") (pinfunction "1_1") (pintype "passive"))
      (node (ref "L14") (pin "2") (pinfunction "2_2") (pintype "passive"))
      (node (ref "U18") (pin "10") (pinfunction "PH_10") (pintype "passive"))
      (node (ref "U18") (pin "6") (pinfunction "PH_6") (pintype "passive"))
      (node (ref "U18") (pin "7") (pinfunction "PH_7") (pintype "passive"))
      (node (ref "U18") (pin "8") (pinfunction "PH_8") (pintype "passive"))
      (node (ref "U18") (pin "9") (pinfunction "PH_9") (pintype "passive"))
    )
    (net (code "4") (name "Net-(C184-Pad1)") (class "Default")
      (node (ref "C184") (pin "1") (pinfunction "1_1") (pintype "passive"))
      (node (ref "L15") (pin "2") (pinfunction "2_2") (pintype "passive"))
      (node (ref "U19") (pin "10") (pinfunction "PH_10") (pintype "passive"))
      (node (ref "U19") (pin "6") (pinfunction "PH_6") (pintype "passive"))
      (node (ref "U19") (pin "7") (pinfunction "PH_7") (pintype "passive"))
      (node (ref "U19") (pin "8") (pinfunction "PH_8") (pintype "passive"))
      (node (ref "U19") (pin "9") (pinfunction "PH_9") (pintype "passive"))
    )
    (net (code "5") (name "Net-(C191-Pad1)") (class "Default")
      (node (ref "C191") (pin "1") (pinfunction "1_1") (pintype "passive"))
      (node (ref "L16") (pin "2") (pinfunction "2_2") (pintype "passive"))
      (node (ref "U20") (pin "10") (pinfunction "PH_10") (pintype "passive"))
      (node (ref "U20") (pin "6") (pinfunction "PH_6") (pintype "passive"))
      (node (ref "U20") (pin "7") (pinfunction "PH_7") (pintype "passive"))
      (node (ref "U20") (pin "8") (pinfunction "PH_8") (pintype "passive"))
      (node (ref "U20") (pin "9") (pinfunction "PH_9") (pintype "passive"))
    )
    (net (code "6") (name "Net-(U18-BOOT)") (class "Default")
      (node (ref "C155") (pin "2") (pinfunction "2_2") (pintype "passive"))
      (node (ref "U18") (pin "5") (pinfunction "BOOT_5") (pintype "passive"))
    )
    (net (code "7") (name "Net-(U18-VBIAS)") (class "Default")
      (node (ref "C154") (pin "2") (pinfunction "2_2") (pintype "passive"))
      (node (ref "U18") (pin "17") (pinfunction "VBIAS_17") (pintype "passive"))
    )
    (net (code "8") (name "Net-(U18-Vsense)") (class "Default")
      (node (ref "C157") (pin "1") (pinfunction "1_1") (pintype "passive"))
      (node (ref "C158") (pin "2") (pinfunction "2_2") (pintype "passive"))
      (node (ref "C159") (pin "2") (pinfunction "2_2") (pintype "passive"))
      (node (ref "C160") (pin "2") (pinfunction "2_2") (pintype "passive"))
      (node (ref "C161") (pin "2") (pinfunction "2_2") (pintype "passive"))
      (node (ref "L14") (pin "1") (pinfunction "1_1") (pintype "passive"))
      (node (ref "R93") (pin "1") (pinfunction "1_1") (pintype "passive"))
      (node (ref "U18") (pin "2") (pinfunction "Vsense_2") (pintype "passive"))
    )
    (net (code "9") (name "Net-(U19-BOOT)") (class "Default")
      (node (ref "C184") (pin "2") (pinfunction "2_2") (pintype "passive"))
      (node (ref "U19") (pin "5") (pinfunction "BOOT_5") (pintype "passive"))
    )
    (net (code "10") (name "Net-(U19-VBIAS)") (class "Default")
      (node (ref "C183") (pin "2") (pinfunction "2_2") (pintype "passive"))
      (node (ref "U19") (pin "17") (pinfunction "VBIAS_17") (pintype "passive"))
    )
    (net (code "11") (name "Net-(U19-Vsense)") (class "Default")
      (node (ref "C186") (pin "1") (pinfunction "1_1") (pintype "passive"))
      (node (ref "C187") (pin "2") (pinfunction "2_2") (pintype "passive"))
      (node (ref "C188") (pin "2") (pinfunction "2_2") (pintype "passive"))
      (node (ref "C189") (pin "2") (pinfunction "2_2") (pintype "passive"))
      (node (ref "L15") (pin "1") (pinfunction "1_1") (pintype "passive"))
      (node (ref "R94") (pin "1") (pinfunction "1_1") (pintype "passive"))
      (node (ref "U19") (pin "2") (pinfunction "Vsense_2") (pintype "passive"))
    )
    (net (code "12") (name "Net-(U20-BOOT)") (class "Default")
      (node (ref "C191") (pin "2") (pinfunction "2_2") (pintype "passive"))
      (node (ref "U20") (pin "5") (pinfunction "BOOT_5") (pintype "passive"))
    )
    (net (code "13") (name "Net-(U20-VBIAS)") (class "Default")
      (node (ref "C190") (pin "2") (pinfunction "2_2") (pintype "passive"))
      (node (ref "U20") (pin "17") (pinfunction "VBIAS_17") (pintype "passive"))
    )
    (net (code "14") (name "Net-(U20-Vsense)") (class "Default")
      (node (ref "C193") (pin "1") (pinfunction "1_1") (pintype "passive"))
      (node (ref "C194") (pin "2") (pinfunction "2_2") (pintype "passive"))
      (node (ref "C195") (pin "2") (pinfunction "2_2") (pintype "passive"))
      (node (ref "C196") (pin "2") (pinfunction "2_2") (pintype "passive"))
      (node (ref "L16") (pin "1") (pinfunction "1_1") (pintype "passive"))
      (node (ref "R95") (pin "1") (pinfunction "1_1") (pintype "passive"))
      (node (ref "U20") (pin "2") (pinfunction "Vsense_2") (pintype "passive"))
    )
    (net (code "15") (name "Net-(U21-ADJ{slash}SENSE)") (class "Default")
      (node (ref "C198") (pin "1") (pinfunction "1_1") (pintype "passive"))
      (node (ref "C199") (pin "2") (pinfunction "2_2") (pintype "passive"))
      (node (ref "R96") (pin "2") (pinfunction "2_2") (pintype "passive"))
      (node (ref "U21") (pin "1") (pinfunction "OUT_1") (pintype "power_in"))
      (node (ref "U21") (pin "2") (pinfunction "ADJ/SENSE_2") (pintype "input"))
    )
    (net (code "16") (name "VCC1V2") (class "Default")
      (node (ref "C162") (pin "2") (pinfunction "2_2") (pintype "passive"))
      (node (ref "C163") (pin "2") (pinfunction "2_2") (pintype "passive"))
      (node (ref "C164") (pin "2") (pinfunction "2_2") (pintype "passive"))
      (node (ref "C165") (pin "2") (pinfunction "2_2") (pintype "passive"))
      (node (ref "C166") (pin "2") (pinfunction "2_2") (pintype "passive"))
      (node (ref "C167") (pin "2") (pinfunction "2_2") (pintype "passive"))
      (node (ref "C168") (pin "2") (pinfunction "2_2") (pintype "passive"))
      (node (ref "C169") (pin "2") (pinfunction "2_2") (pintype "passive"))
      (node (ref "C170") (pin "2") (pinfunction "2_2") (pintype "passive"))
      (node (ref "C171") (pin "2") (pinfunction "2_2") (pintype "passive"))
      (node (ref "C172") (pin "2") (pinfunction "2_2") (pintype "passive"))
      (node (ref "C173") (pin "2") (pinfunction "2_2") (pintype "passive"))
      (node (ref "C174") (pin "2") (pinfunction "2_2") (pintype "passive"))
      (node (ref "C175") (pin "2") (pinfunction "2_2") (pintype "passive"))
      (node (ref "C176") (pin "2") (pinfunction "2_2") (pintype "passive"))
      (node (ref "C177") (pin "2") (pinfunction "2_2") (pintype "passive"))
      (node (ref "C178") (pin "2") (pinfunction "2_2") (pintype "passive"))
      (node (ref "C179") (pin "2") (pinfunction "2_2") (pintype "passive"))
      (node (ref "C180") (pin "2") (pinfunction "2_2") (pintype "passive"))
      (node (ref "C181") (pin "2") (pinfunction "2_2") (pintype "passive"))
      (node (ref "C182") (pin "2") (pinfunction "2_2") (pintype "passive"))
      (node (ref "R95") (pin "2") (pinfunction "2_2") (pintype "passive"))
      (node (ref "U1") (pin "J10") (pinfunction "VCCINT_J10") (pintype "power_in"))
      (node (ref "U1") (pin "J12") (pinfunction "VCCINT_J12") (pintype "power_in"))
      (node (ref "U1") (pin "J14") (pinfunction "VCCINT_J14") (pintype "power_in"))
      (node (ref "U1") (pin "J8") (pinfunction "VCCINT_J8") (pintype "power_in"))
      (node (ref "U1") (pin "K11") (pinfunction "VCCINT_K11") (pintype "power_in"))
      (node (ref "U1") (pin "K13") (pinfunction "VCCINT_K13") (pintype "power_in"))
      (node (ref "U1") (pin "K9") (pinfunction "VCCINT_K9") (pintype "power_in"))
      (node (ref "U1") (pin "L10") (pinfunction "VCCINT_L10") (pintype "power_in"))
      (node (ref "U1") (pin "L12") (pinfunction "VCCINT_L12") (pintype "power_in"))
      (node (ref "U1") (pin "L14") (pinfunction "VCCINT_L14") (pintype "power_in"))
      (node (ref "U1") (pin "M11") (pinfunction "VCCINT_M11") (pintype "power_in"))
      (node (ref "U1") (pin "M13") (pinfunction "VCCINT_M13") (pintype "power_in"))
      (node (ref "U1") (pin "M9") (pinfunction "VCCINT_M9") (pintype "power_in"))
      (node (ref "U1") (pin "N10") (pinfunction "VCCINT_N10") (pintype "power_in"))
      (node (ref "U1") (pin "N12") (pinfunction "VCCINT_N12") (pintype "power_in"))
      (node (ref "U1") (pin "N14") (pinfunction "VCCINT_N14") (pintype "power_in"))
      (node (ref "U1") (pin "P11") (pinfunction "VCCINT_P11") (pintype "power_in"))
      (node (ref "U1") (pin "P13") (pinfunction "VCCINT_P13") (pintype "power_in"))
      (node (ref "U1") (pin "P9") (pinfunction "VCCINT_P9") (pintype "power_in"))
      (node (ref "U1") (pin "R14") (pinfunction "VCCINT_R14") (pintype "power_in"))
    )
    (net (code "17") (name "VCC2V5") (class "Default")
      (node (ref "R96") (pin "1") (pinfunction "1_1") (pintype "passive"))
    )
    (net (code "18") (name "VCC3V3") (class "Default")
      (node (ref "C100") (pin "2") (pinfunction "2_2") (pintype "passive"))
      (node (ref "C101") (pin "2") (pinfunction "2_2") (pintype "passive"))
      (node (ref "C102") (pin "2") (pinfunction "2_2") (pintype "passive"))
      (node (ref "C103") (pin "2") (pinfunction "2_2") (pintype "passive"))
      (node (ref "C104") (pin "2") (pinfunction "2_2") (pintype "passive"))
      (node (ref "C105") (pin "2") (pinfunction "2_2") (pintype "passive"))
      (node (ref "C106") (pin "2") (pinfunction "2_2") (pintype "passive"))
      (node (ref "C107") (pin "2") (pinfunction "2_2") (pintype "passive"))
      (node (ref "C108") (pin "2") (pinfunction "2_2") (pintype "passive"))
      (node (ref "C109") (pin "2") (pinfunction "2_2") (pintype "passive"))
      (node (ref "C110") (pin "2") (pinfunction "2_2") (pintype "passive"))
      (node (ref "C111") (pin "2") (pinfunction "2_2") (pintype "passive"))
      (node (ref "C112") (pin "2") (pinfunction "2_2") (pintype "passive"))
      (node (ref "C113") (pin "2") (pinfunction "2_2") (pintype "passive"))
      (node (ref "C114") (pin "2") (pinfunction "2_2") (pintype "passive"))
      (node (ref "C115") (pin "2") (pinfunction "2_2") (pintype "passive"))
      (node (ref "C116") (pin "2") (pinfunction "2_2") (pintype "passive"))
      (node (ref "C117") (pin "2") (pinfunction "2_2") (pintype "passive"))
      (node (ref "C118") (pin "2") (pinfunction "2_2") (pintype "passive"))
      (node (ref "C119") (pin "2") (pinfunction "2_2") (pintype "passive"))
      (node (ref "C120") (pin "2") (pinfunction "2_2") (pintype "passive"))
      (node (ref "C121") (pin "2") (pinfunction "2_2") (pintype "passive"))
      (node (ref "C122") (pin "2") (pinfunction "2_2") (pintype "passive"))
      (node (ref "C123") (pin "2") (pinfunction "2_2") (pintype "passive"))
      (node (ref "C124") (pin "2") (pinfunction "2_2") (pintype "passive"))
      (node (ref "C125") (pin "2") (pinfunction "2_2") (pintype "passive"))
      (node (ref "C126") (pin "2") (pinfunction "2_2") (pintype "passive"))
      (node (ref "C127") (pin "2") (pinfunction "2_2") (pintype "passive"))
      (node (ref "C128") (pin "2") (pinfunction "2_2") (pintype "passive"))
      (node (ref "C129") (pin "2") (pinfunction "2_2") (pintype "passive"))
      (node (ref "C130") (pin "2") (pinfunction "2_2") (pintype "passive"))
      (node (ref "C131") (pin "2") (pinfunction "2_2") (pintype "passive"))
      (node (ref "C132") (pin "2") (pinfunction "2_2") (pintype "passive"))
      (node (ref "C133") (pin "2") (pinfunction "2_2") (pintype "passive"))
      (node (ref "C134") (pin "2") (pinfunction "2_2") (pintype "passive"))
      (node (ref "C135") (pin "2") (pinfunction "2_2") (pintype "passive"))
      (node (ref "C136") (pin "2") (pinfunction "2_2") (pintype "passive"))
      (node (ref "C137") (pin "2") (pinfunction "2_2") (pintype "passive"))
      (node (ref "C138") (pin "2") (pinfunction "2_2") (pintype "passive"))
      (node (ref "C139") (pin "2") (pinfunction "2_2") (pintype "passive"))
      (node (ref "C140") (pin "2") (pinfunction "2_2") (pintype "passive"))
      (node (ref "C141") (pin "2") (pinfunction "2_2") (pintype "passive"))
      (node (ref "C142") (pin "2") (pinfunction "2_2") (pintype "passive"))
      (node (ref "C143") (pin "2") (pinfunction "2_2") (pintype "passive"))
      (node (ref "C144") (pin "2") (pinfunction "2_2") (pintype "passive"))
      (node (ref "C145") (pin "2") (pinfunction "2_2") (pintype "passive"))
      (node (ref "C146") (pin "2") (pinfunction "2_2") (pintype "passive"))
      (node (ref "C147") (pin "2") (pinfunction "2_2") (pintype "passive"))
      (node (ref "C148") (pin "2") (pinfunction "2_2") (pintype "passive"))
      (node (ref "C149") (pin "2") (pinfunction "2_2") (pintype "passive"))
      (node (ref "C150") (pin "2") (pinfunction "2_2") (pintype "passive"))
      (node (ref "C151") (pin "2") (pinfunction "2_2") (pintype "passive"))
      (node (ref "C152") (pin "2") (pinfunction "2_2") (pintype "passive"))
      (node (ref "C153") (pin "2") (pinfunction "2_2") (pintype "passive"))
      (node (ref "C94") (pin "2") (pinfunction "2_2") (pintype "passive"))
      (node (ref "C95") (pin "2") (pinfunction "2_2") (pintype "passive"))
      (node (ref "C96") (pin "2") (pinfunction "2_2") (pintype "passive"))
      (node (ref "C97") (pin "2") (pinfunction "2_2") (pintype "passive"))
      (node (ref "C98") (pin "2") (pinfunction "2_2") (pintype "passive"))
      (node (ref "C99") (pin "2") (pinfunction "2_2") (pintype "passive"))
      (node (ref "R94") (pin "2") (pinfunction "2_2") (pintype "passive"))
      (node (ref "U1") (pin "AA11") (pinfunction "VCCO_2_AA11") (pintype "power_in"))
      (node (ref "U1") (pin "AA15") (pinfunction "VCCO_2_AA15") (pintype "power_in"))
      (node (ref "U1") (pin "AA19") (pinfunction "VCCO_2_AA19") (pintype "power_in"))
      (node (ref "U1") (pin "AA3") (pinfunction "VCCO_2_AA3") (pintype "power_in"))
      (node (ref "U1") (pin "AA7") (pinfunction "VCCO_2_AA7") (pintype "power_in"))
      (node (ref "U1") (pin "B11") (pinfunction "VCCO_0_B11") (pintype "power_in"))
      (node (ref "U1") (pin "B15") (pinfunction "VCCO_0_B15") (pintype "power_in"))
      (node (ref "U1") (pin "B19") (pinfunction "VCCO_0_B19") (pintype "power_in"))
      (node (ref "U1") (pin "B4") (pinfunction "VCCO_0_B4") (pintype "power_in"))
      (node (ref "U1") (pin "B7") (pinfunction "VCCO_0_B7") (pintype "power_in"))
      (node (ref "U1") (pin "C2") (pinfunction "VCCO_3_C2") (pintype "power_in"))
      (node (ref "U1") (pin "C21") (pinfunction "VCCO_1_C21") (pintype "power_in"))
      (node (ref "U1") (pin "D16") (pinfunction "VCCAUX_D16") (pintype "power_in"))
      (node (ref "U1") (pin "E13") (pinfunction "VCCO_0_E13") (pintype "power_in"))
      (node (ref "U1") (pin "E17") (pinfunction "VCCO_0_E17") (pintype "power_in"))
      (node (ref "U1") (pin "E19") (pinfunction "VCCO_1_E19") (pintype "power_in"))
      (node (ref "U1") (pin "E9") (pinfunction "VCCO_0_E9") (pintype "power_in"))
      (node (ref "U1") (pin "F11") (pinfunction "VCCAUX_F11") (pintype "power_in"))
      (node (ref "U1") (pin "F4") (pinfunction "VCCO_3_F4") (pintype "power_in"))
      (node (ref "U1") (pin "F6") (pinfunction "VCCO_3_F6") (pintype "power_in"))
      (node (ref "U1") (pin "G10") (pinfunction "VCCO_0_G10") (pintype "power_in"))
      (node (ref "U1") (pin "G12") (pinfunction "VCCAUX_G12") (pintype "power_in"))
      (node (ref "U1") (pin "G14") (pinfunction "VCCO_0_G14") (pintype "power_in"))
      (node (ref "U1") (pin "G2") (pinfunction "VCCO_3_G2") (pintype "power_in"))
      (node (ref "U1") (pin "G21") (pinfunction "VCCO_1_G21") (pintype "power_in"))
      (node (ref "U1") (pin "H15") (pinfunction "VCCAUX_H15") (pintype "power_in"))
      (node (ref "U1") (pin "H9") (pinfunction "VCCAUX_H9") (pintype "power_in"))
      (node (ref "U1") (pin "J18") (pinfunction "VCCO_1_J18") (pintype "power_in"))
      (node (ref "U1") (pin "J5") (pinfunction "VCCO_3_J5") (pintype "power_in"))
      (node (ref "U1") (pin "K15") (pinfunction "VCCAUX_K15") (pintype "power_in"))
      (node (ref "U1") (pin "L16") (pinfunction "VCCO_1_L16") (pintype "power_in"))
      (node (ref "U1") (pin "L2") (pinfunction "VCCO_3_L2") (pintype "power_in"))
      (node (ref "U1") (pin "L21") (pinfunction "VCCO_1_L21") (pintype "power_in"))
      (node (ref "U1") (pin "L7") (pinfunction "VCCO_3_L7") (pintype "power_in"))
      (node (ref "U1") (pin "L8") (pinfunction "VCCAUX_L8") (pintype "power_in"))
      (node (ref "U1") (pin "M15") (pinfunction "VCCAUX_M15") (pintype "power_in"))
      (node (ref "U1") (pin "N18") (pinfunction "VCCO_1_N18") (pintype "power_in"))
      (node (ref "U1") (pin "N5") (pinfunction "VCCO_3_N5") (pintype "power_in"))
      (node (ref "U1") (pin "N8") (pinfunction "VCCAUX_N8") (pintype "power_in"))
      (node (ref "U1") (pin "R10") (pinfunction "VCCAUX_R10") (pintype "power_in"))
      (node (ref "U1") (pin "R12") (pinfunction "VCCAUX_R12") (pintype "power_in"))
      (node (ref "U1") (pin "R2") (pinfunction "VCCO_3_R2") (pintype "power_in"))
      (node (ref "U1") (pin "R21") (pinfunction "VCCO_1_R21") (pintype "power_in"))
      (node (ref "U1") (pin "R6") (pinfunction "VCCAUX_R6") (pintype "power_in"))
      (node (ref "U1") (pin "T13") (pinfunction "VCCO_2_T13") (pintype "power_in"))
      (node (ref "U1") (pin "T9") (pinfunction "VCCO_2_T9") (pintype "power_in"))
      (node (ref "U1") (pin "U11") (pinfunction "VCCAUX_U11") (pintype "power_in"))
      (node (ref "U1") (pin "U18") (pinfunction "VCCO_1_U18") (pintype "power_in"))
      (node (ref "U1") (pin "U5") (pinfunction "VCCO_3_U5") (pintype "power_in"))
      (node (ref "U1") (pin "V12") (pinfunction "VCCO_2_V12") (pintype "power_in"))
      (node (ref "U1") (pin "V16") (pinfunction "VCCO_2_V16") (pintype "power_in"))
      (node (ref "U1") (pin "V6") (pinfunction "VCCAUX_V6") (pintype "power_in"))
      (node (ref "U1") (pin "V8") (pinfunction "VCCO_2_V8") (pintype "power_in"))
      (node (ref "U1") (pin "W2") (pinfunction "VCCO_3_W2") (pintype "power_in"))
      (node (ref "U1") (pin "W21") (pinfunction "VCCO_1_W21") (pintype "power_in"))
      (node (ref "U1") (pin "W5") (pinfunction "VCCO_2_W5") (pintype "power_in"))
    )
    (net (code "19") (name "VCC5V") (class "Default")
      (node (ref "C156") (pin "1") (pinfunction "1_1") (pintype "passive"))
      (node (ref "C185") (pin "1") (pinfunction "1_1") (pintype "passive"))
      (node (ref "C192") (pin "1") (pinfunction "1_1") (pintype "passive"))
      (node (ref "C197") (pin "1") (pinfunction "1_1") (pintype "passive"))
      (node (ref "U18") (pin "14") (pinfunction "VIN_14") (pintype "passive"))
      (node (ref "U18") (pin "15") (pinfunction "VIN_15") (pintype "passive"))
      (node (ref "U18") (pin "16") (pinfunction "VIN_16") (pintype "passive"))
      (node (ref "U18") (pin "19") (pinfunction "FSEL_19") (pintype "passive"))
      (node (ref "U19") (pin "14") (pinfunction "VIN_14") (pintype "passive"))
      (node (ref "U19") (pin "15") (pinfunction "VIN_15") (pintype "passive"))
      (node (ref "U19") (pin "16") (pinfunction "VIN_16") (pintype "passive"))
      (node (ref "U19") (pin "19") (pinfunction "FSEL_19") (pintype "passive"))
      (node (ref "U20") (pin "14") (pinfunction "VIN_14") (pintype "passive"))
      (node (ref "U20") (pin "15") (pinfunction "VIN_15") (pintype "passive"))
      (node (ref "U20") (pin "16") (pinfunction "VIN_16") (pintype "passive"))
      (node (ref "U20") (pin "19") (pinfunction "FSEL_19") (pintype "passive"))
      (node (ref "U21") (pin "5") (pinfunction "~{SHDN}_5") (pintype "input"))
      (node (ref "U21") (pin "8") (pinfunction "IN_8") (pintype "power_in"))
      (node (ref "X3") (pin "1") (pinfunction "1_1") (pintype "passive"))
    )
    (net (code "20") (name "unconnected-(U1H-NC-PadD12)") (class "Default")
      (node (ref "U1") (pin "D12") (pinfunction "NC_D12") (pintype "passive"))
    )
    (net (code "21") (name "unconnected-(U1H-NC-PadD13)") (class "Default")
      (node (ref "U1") (pin "D13") (pinfunction "NC_D13") (pintype "passive"))
    )
    (net (code "22") (name "unconnected-(U1H-NC-PadE8)") (class "Default")
      (node (ref "U1") (pin "E8") (pinfunction "NC_E8") (pintype "passive"))
    )
    (net (code "23") (name "unconnected-(U1H-NC-PadE10)") (class "Default")
      (node (ref "U1") (pin "E10") (pinfunction "NC_E10") (pintype "passive"))
    )
    (net (code "24") (name "unconnected-(U1H-NC-PadE12)") (class "Default")
      (node (ref "U1") (pin "E12") (pinfunction "NC_E12") (pintype "passive"))
    )
    (net (code "25") (name "unconnected-(U1H-NC-PadE14)") (class "Default")
      (node (ref "U1") (pin "E14") (pinfunction "NC_E14") (pintype "passive"))
    )
    (net (code "26") (name "unconnected-(U1H-NC-PadF8)") (class "Default")
      (node (ref "U1") (pin "F8") (pinfunction "NC_F8") (pintype "passive"))
    )
    (net (code "27") (name "unconnected-(U1H-NC-PadF9)") (class "Default")
      (node (ref "U1") (pin "F9") (pinfunction "NC_F9") (pintype "passive"))
    )
    (net (code "28") (name "unconnected-(U1H-NC-PadF10)") (class "Default")
      (node (ref "U1") (pin "F10") (pinfunction "NC_F10") (pintype "passive"))
    )
    (net (code "29") (name "unconnected-(U1H-NC-PadF12)") (class "Default")
      (node (ref "U1") (pin "F12") (pinfunction "NC_F12") (pintype "passive"))
    )
    (net (code "30") (name "unconnected-(U1H-NC-PadF13)") (class "Default")
      (node (ref "U1") (pin "F13") (pinfunction "NC_F13") (pintype "passive"))
    )
    (net (code "31") (name "unconnected-(U1H-NC-PadF14)") (class "Default")
      (node (ref "U1") (pin "F14") (pinfunction "NC_F14") (pintype "passive"))
    )
    (net (code "32") (name "unconnected-(U1H-NC-PadF15)") (class "Default")
      (node (ref "U1") (pin "F15") (pinfunction "NC_F15") (pintype "passive"))
    )
    (net (code "33") (name "unconnected-(U1H-NC-PadG8)") (class "Default")
      (node (ref "U1") (pin "G8") (pinfunction "NC_G8") (pintype "passive"))
    )
    (net (code "34") (name "unconnected-(U1H-NC-PadG9)") (class "Default")
      (node (ref "U1") (pin "G9") (pinfunction "NC_G9") (pintype "passive"))
    )
    (net (code "35") (name "unconnected-(U1H-NC-PadG11)") (class "Default")
      (node (ref "U1") (pin "G11") (pinfunction "NC_G11") (pintype "passive"))
    )
    (net (code "36") (name "unconnected-(U1H-NC-PadG13)") (class "Default")
      (node (ref "U1") (pin "G13") (pinfunction "NC_G13") (pintype "passive"))
    )
    (net (code "37") (name "unconnected-(U1H-NC-PadH10)") (class "Default")
      (node (ref "U1") (pin "H10") (pinfunction "NC_H10") (pintype "passive"))
    )
    (net (code "38") (name "unconnected-(U1H-NC-PadH11)") (class "Default")
      (node (ref "U1") (pin "H11") (pinfunction "NC_H11") (pintype "passive"))
    )
    (net (code "39") (name "unconnected-(U1H-NC-PadH12)") (class "Default")
      (node (ref "U1") (pin "H12") (pinfunction "NC_H12") (pintype "passive"))
    )
    (net (code "40") (name "unconnected-(U1H-NC-PadH13)") (class "Default")
      (node (ref "U1") (pin "H13") (pinfunction "NC_H13") (pintype "passive"))
    )
    (net (code "41") (name "unconnected-(U1H-NC-PadH14)") (class "Default")
      (node (ref "U1") (pin "H14") (pinfunction "NC_H14") (pintype "passive"))
    )
    (net (code "42") (name "unconnected-(U1H-NC-PadP15)") (class "Default")
      (node (ref "U1") (pin "P15") (pinfunction "NC_P15") (pintype "passive"))
    )
    (net (code "43") (name "unconnected-(U1H-NC-PadP16)") (class "Default")
      (node (ref "U1") (pin "P16") (pinfunction "NC_P16") (pintype "passive"))
    )
    (net (code "44") (name "unconnected-(U1H-NC-PadR17)") (class "Default")
      (node (ref "U1") (pin "R17") (pinfunction "NC_R17") (pintype "passive"))
    )
    (net (code "45") (name "unconnected-(U18-NC-Pad3)") (class "Default")
      (node (ref "U18") (pin "3") (pinfunction "NC_3") (pintype "passive"))
    )
    (net (code "46") (name "unconnected-(U18-PWRGD-Pad4)") (class "Default")
      (node (ref "U18") (pin "4") (pinfunction "PWRGD_4") (pintype "passive"))
    )
    (net (code "47") (name "unconnected-(U18-RT-Pad20)") (class "Default")
      (node (ref "U18") (pin "20") (pinfunction "RT_20") (pintype "passive"))
    )
    (net (code "48") (name "unconnected-(U18-SS{slash}ENA-Pad18)") (class "Default")
      (node (ref "U18") (pin "18") (pinfunction "SS/ENA_18") (pintype "passive"))
    )
    (net (code "49") (name "unconnected-(U19-NC-Pad3)") (class "Default")
      (node (ref "U19") (pin "3") (pinfunction "NC_3") (pintype "passive"))
    )
    (net (code "50") (name "unconnected-(U19-PWRGD-Pad4)") (class "Default")
      (node (ref "U19") (pin "4") (pinfunction "PWRGD_4") (pintype "passive"))
    )
    (net (code "51") (name "unconnected-(U19-RT-Pad20)") (class "Default")
      (node (ref "U19") (pin "20") (pinfunction "RT_20") (pintype "passive"))
    )
    (net (code "52") (name "unconnected-(U19-SS{slash}ENA-Pad18)") (class "Default")
      (node (ref "U19") (pin "18") (pinfunction "SS/ENA_18") (pintype "passive"))
    )
    (net (code "53") (name "unconnected-(U20-NC-Pad3)") (class "Default")
      (node (ref "U20") (pin "3") (pinfunction "NC_3") (pintype "passive"))
    )
    (net (code "54") (name "unconnected-(U20-PWRGD-Pad4)") (class "Default")
      (node (ref "U20") (pin "4") (pinfunction "PWRGD_4") (pintype "passive"))
    )
    (net (code "55") (name "unconnected-(U20-RT-Pad20)") (class "Default")
      (node (ref "U20") (pin "20") (pinfunction "RT_20") (pintype "passive"))
    )
    (net (code "56") (name "unconnected-(U20-SS{slash}ENA-Pad18)") (class "Default")
      (node (ref "U20") (pin "18") (pinfunction "SS/ENA_18") (pintype "passive"))
    )
    (net (code "57") (name "unconnected-(U21-NC-Pad4)") (class "Default")
      (node (ref "U21") (pin "4") (pinfunction "NC_4") (pintype "passive"))
    )
  )
)
